# TCA9548A.net
KiCad netlist of a schematic drawn in Altium Designer
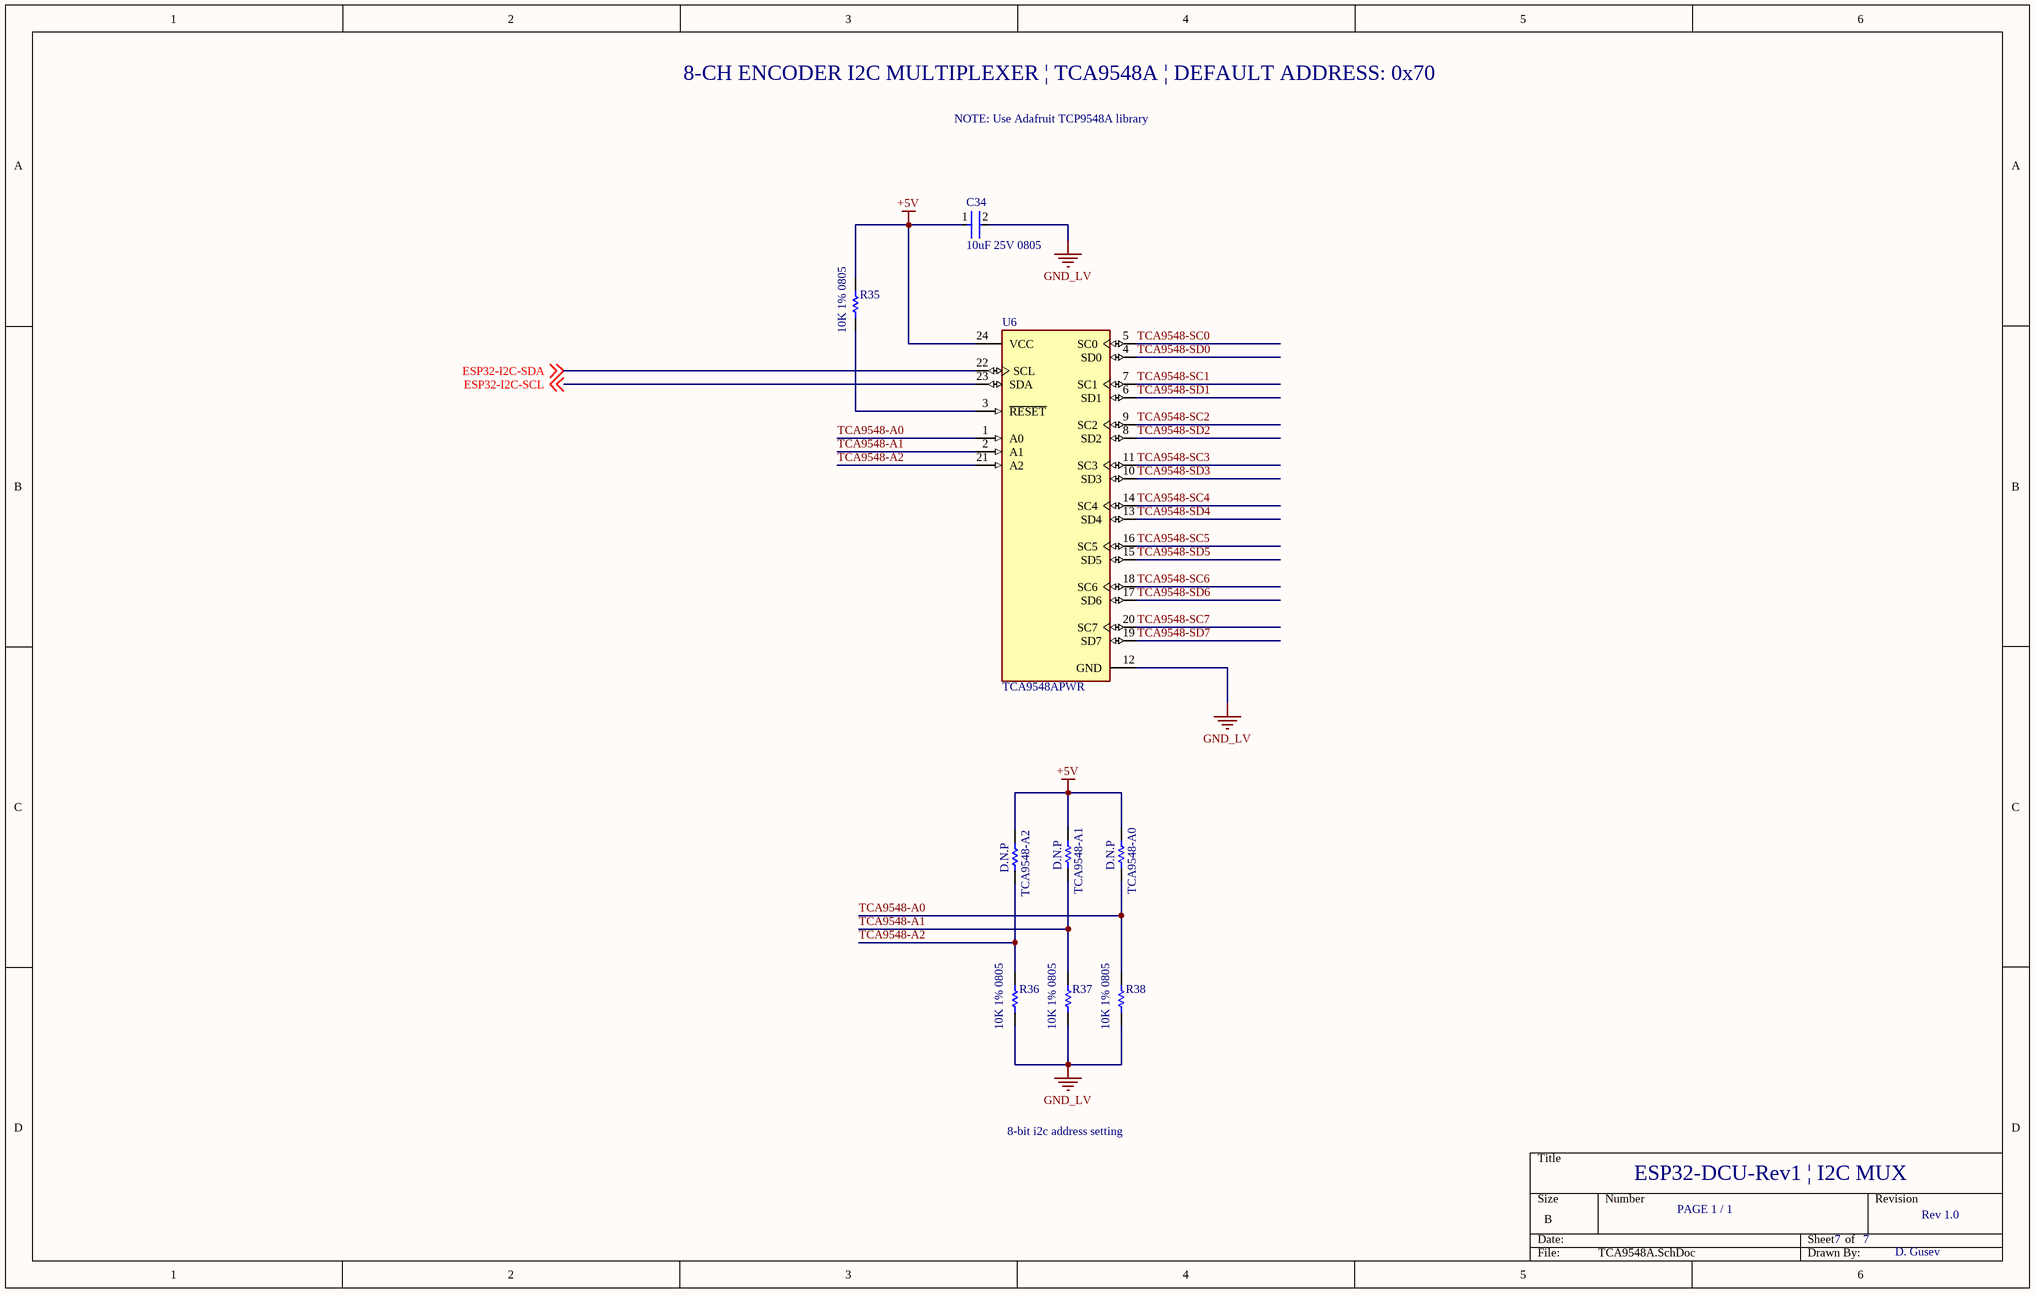
[diagram p0: TCA9548A.SchDoc]

(export (version "E")
  (design (tool "Eeschema 10.0.6"))
  (components
    (comp (ref "C34")
      (value "10uF 25V 0805")
      (footprint "FP-GRM21B-0_15-IPC_B")
      (description "Chip Multilayer Ceramic Capacitors for General Purpose, 0805, 10uF, X5R, 15%, 10%, 25V")
      (fields (field (name "VOLTAGE") "25V") (field (name "TOLERANCE") "10%"))
      (libsource (lib "Altium Content Vault") (part "b4654b650e69147ec39a6b967a45e02"))
    )
    (comp (ref "R35")
      (value "10K 1% 0805")
      (footprint "RESC2013X60X35ML10T20")
      (description "Chip Resistor, 10 KOhm, +/- 5%, 0.125 W, -55 to 155 degC, 0805 (2012 Metric), RoHS, Tape and Reel")
      (fields (field (name "MANUFACTURER") "Yageo"))
      (libsource (lib "Altium Content Vault") (part "RES-2"))
    )
    (comp (ref "R36")
      (value "10K 1% 0805")
      (footprint "RESC2013X60X35ML10T20")
      (description "Chip Resistor, 10 KOhm, +/- 5%, 0.125 W, -55 to 155 degC, 0805 (2012 Metric), RoHS, Tape and Reel")
      (fields (field (name "MANUFACTURER") "Yageo"))
      (libsource (lib "Altium Content Vault") (part "RES-2"))
    )
    (comp (ref "R37")
      (value "10K 1% 0805")
      (footprint "RESC2013X60X35ML10T20")
      (description "Chip Resistor, 10 KOhm, +/- 5%, 0.125 W, -55 to 155 degC, 0805 (2012 Metric), RoHS, Tape and Reel")
      (fields (field (name "MANUFACTURER") "Yageo"))
      (libsource (lib "Altium Content Vault") (part "RES-2"))
    )
    (comp (ref "R38")
      (value "10K 1% 0805")
      (footprint "RESC2013X60X35ML10T20")
      (description "Chip Resistor, 10 KOhm, +/- 5%, 0.125 W, -55 to 155 degC, 0805 (2012 Metric), RoHS, Tape and Reel")
      (fields (field (name "MANUFACTURER") "Yageo"))
      (libsource (lib "Altium Content Vault") (part "RES-2"))
    )
    (comp (ref "TCA9548-A0")
      (value "D.N.P")
      (footprint "RESC2013X60X35LL10T20")
      (description "Chip Resistor, 1 Ohm, +/- 1%, 125 mW, -55 to 155 degC, 0805 (2012 Metric), RoHS, Tape and Reel")
      (fields (field (name "MANUFACTURER") "Yageo"))
      (libsource (lib "Altium Content Vault") (part "RES-2"))
    )
    (comp (ref "TCA9548-A1")
      (value "D.N.P")
      (footprint "RESC2013X60X35LL10T20")
      (description "Chip Resistor, 1 Ohm, +/- 1%, 125 mW, -55 to 155 degC, 0805 (2012 Metric), RoHS, Tape and Reel")
      (fields (field (name "MANUFACTURER") "Yageo"))
      (libsource (lib "Altium Content Vault") (part "RES-2"))
    )
    (comp (ref "TCA9548-A2")
      (value "D.N.P")
      (footprint "RESC2013X60X35LL10T20")
      (description "Chip Resistor, 1 Ohm, +/- 1%, 125 mW, -55 to 155 degC, 0805 (2012 Metric), RoHS, Tape and Reel")
      (fields (field (name "MANUFACTURER") "Yageo"))
      (libsource (lib "Altium Content Vault") (part "RES-2"))
    )
    (comp (ref "U6")
      (value "TCA9548APWR")
      (footprint "FP-PW0024A-MFG")
      (description "IC I2C SW 8CH W/RESET 24TSSOP")
      (fields
        (field (name "MANUFACTURER") "Texas Instruments")
        (field (name "OCTOPART") "https://octopart.com/tca9548apwr-texas+instruments-22266789")
      )
      (libsource (lib "Altium Content Vault") (part "aab65143522579f0e88a32f493a4230"))
    )
  )
  (nets
    (net (code "1") (name "+5V") (class "Default")
      (node (ref "C34") (pin "1") (pinfunction "1_1") (pintype "passive"))
      (node (ref "R35") (pin "2") (pinfunction "2_2") (pintype "passive"))
      (node (ref "TCA9548-A0") (pin "2") (pinfunction "2_2") (pintype "passive"))
      (node (ref "TCA9548-A1") (pin "2") (pinfunction "2_2") (pintype "passive"))
      (node (ref "TCA9548-A2") (pin "2") (pinfunction "2_2") (pintype "passive"))
      (node (ref "U6") (pin "24") (pinfunction "VCC_24") (pintype "power_in"))
    )
    (net (code "2") (name "/TCA9548-A0") (class "Default")
      (node (ref "R38") (pin "1") (pinfunction "1_1") (pintype "passive"))
      (node (ref "TCA9548-A0") (pin "1") (pinfunction "1_1") (pintype "passive"))
      (node (ref "U6") (pin "1") (pinfunction "A0_1") (pintype "input"))
    )
    (net (code "3") (name "/TCA9548-A1") (class "Default")
      (node (ref "R37") (pin "1") (pinfunction "1_1") (pintype "passive"))
      (node (ref "TCA9548-A1") (pin "1") (pinfunction "1_1") (pintype "passive"))
      (node (ref "U6") (pin "2") (pinfunction "A1_2") (pintype "input"))
    )
    (net (code "4") (name "/TCA9548-A2") (class "Default")
      (node (ref "R36") (pin "1") (pinfunction "1_1") (pintype "passive"))
      (node (ref "TCA9548-A2") (pin "1") (pinfunction "1_1") (pintype "passive"))
      (node (ref "U6") (pin "21") (pinfunction "A2_21") (pintype "input"))
    )
    (net (code "5") (name "/TCA9548-SC0") (class "Default")
      (node (ref "U6") (pin "5") (pinfunction "SC0_5") (pintype "bidirectional"))
    )
    (net (code "6") (name "/TCA9548-SC1") (class "Default")
      (node (ref "U6") (pin "7") (pinfunction "SC1_7") (pintype "bidirectional"))
    )
    (net (code "7") (name "/TCA9548-SC2") (class "Default")
      (node (ref "U6") (pin "9") (pinfunction "SC2_9") (pintype "bidirectional"))
    )
    (net (code "8") (name "/TCA9548-SC3") (class "Default")
      (node (ref "U6") (pin "11") (pinfunction "SC3_11") (pintype "bidirectional"))
    )
    (net (code "9") (name "/TCA9548-SC4") (class "Default")
      (node (ref "U6") (pin "14") (pinfunction "SC4_14") (pintype "bidirectional"))
    )
    (net (code "10") (name "/TCA9548-SC5") (class "Default")
      (node (ref "U6") (pin "16") (pinfunction "SC5_16") (pintype "bidirectional"))
    )
    (net (code "11") (name "/TCA9548-SC6") (class "Default")
      (node (ref "U6") (pin "18") (pinfunction "SC6_18") (pintype "bidirectional"))
    )
    (net (code "12") (name "/TCA9548-SC7") (class "Default")
      (node (ref "U6") (pin "20") (pinfunction "SC7_20") (pintype "bidirectional"))
    )
    (net (code "13") (name "/TCA9548-SD0") (class "Default")
      (node (ref "U6") (pin "4") (pinfunction "SD0_4") (pintype "bidirectional"))
    )
    (net (code "14") (name "/TCA9548-SD1") (class "Default")
      (node (ref "U6") (pin "6") (pinfunction "SD1_6") (pintype "bidirectional"))
    )
    (net (code "15") (name "/TCA9548-SD2") (class "Default")
      (node (ref "U6") (pin "8") (pinfunction "SD2_8") (pintype "bidirectional"))
    )
    (net (code "16") (name "/TCA9548-SD3") (class "Default")
      (node (ref "U6") (pin "10") (pinfunction "SD3_10") (pintype "bidirectional"))
    )
    (net (code "17") (name "/TCA9548-SD4") (class "Default")
      (node (ref "U6") (pin "13") (pinfunction "SD4_13") (pintype "bidirectional"))
    )
    (net (code "18") (name "/TCA9548-SD5") (class "Default")
      (node (ref "U6") (pin "15") (pinfunction "SD5_15") (pintype "bidirectional"))
    )
    (net (code "19") (name "/TCA9548-SD6") (class "Default")
      (node (ref "U6") (pin "17") (pinfunction "SD6_17") (pintype "bidirectional"))
    )
    (net (code "20") (name "/TCA9548-SD7") (class "Default")
      (node (ref "U6") (pin "19") (pinfunction "SD7_19") (pintype "bidirectional"))
    )
    (net (code "21") (name "ESP32-I2C-SCL") (class "Default")
      (node (ref "U6") (pin "23") (pinfunction "SDA_23") (pintype "bidirectional"))
    )
    (net (code "22") (name "ESP32-I2C-SDA") (class "Default")
      (node (ref "U6") (pin "22") (pinfunction "SCL_22") (pintype "bidirectional"))
    )
    (net (code "23") (name "GND_LV") (class "Default")
      (node (ref "C34") (pin "2") (pinfunction "2_2") (pintype "passive"))
      (node (ref "R36") (pin "2") (pinfunction "2_2") (pintype "passive"))
      (node (ref "R37") (pin "2") (pinfunction "2_2") (pintype "passive"))
      (node (ref "R38") (pin "2") (pinfunction "2_2") (pintype "passive"))
      (node (ref "U6") (pin "12") (pinfunction "GND_12") (pintype "power_in"))
    )
    (net (code "24") (name "Net-(U6-~{RESET})") (class "Default")
      (node (ref "R35") (pin "1") (pinfunction "1_1") (pintype "passive"))
      (node (ref "U6") (pin "3") (pinfunction "~{RESET}_3") (pintype "input"))
    )
  )
)
